# ADAPTER.net
KiCad netlist of a schematic drawn in EAGLE
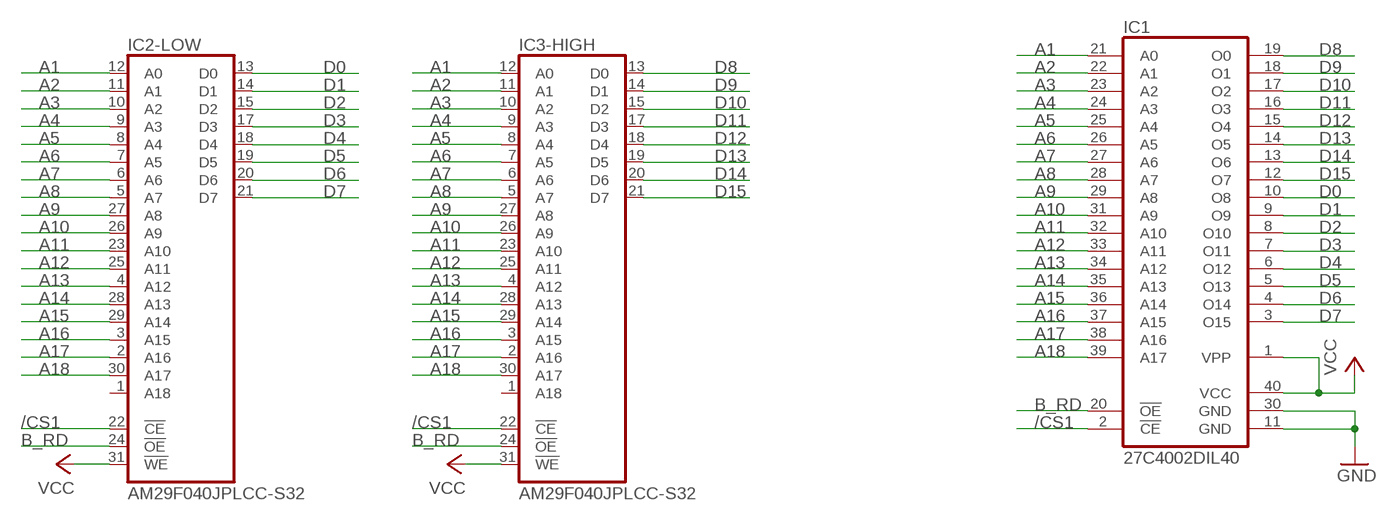
[diagram p0: schematic, sheet 1]

(export (version "E")
  (design (tool "Eeschema 10.0.6"))
  (components
    (comp (ref "IC1")
      (value "27C4002DIL40")
      (footprint "eagle-import:DIL40")
      (libsource (lib "eagle-import") (part "27C4002DIL40"))
    )
    (comp (ref "IC2-LOW")
      (value "AM29F040JPLCC-S32")
      (footprint "eagle-import:PLCC-S32")
      (libsource (lib "eagle-import") (part "AM29F040JPLCC-S32"))
    )
    (comp (ref "IC3-HIGH")
      (value "AM29F040JPLCC-S32")
      (footprint "eagle-import:PLCC-S32")
      (libsource (lib "eagle-import") (part "AM29F040JPLCC-S32"))
    )
  )
  (nets
    (net (code "1") (name "/A1") (class "Default")
      (node (ref "IC1") (pin "21") (pinfunction "A0_21") (pintype "input"))
      (node (ref "IC2-LOW") (pin "12") (pinfunction "A0_12") (pintype "input"))
      (node (ref "IC3-HIGH") (pin "12") (pinfunction "A0_12") (pintype "input"))
    )
    (net (code "2") (name "/A2") (class "Default")
      (node (ref "IC1") (pin "22") (pinfunction "A1_22") (pintype "input"))
      (node (ref "IC2-LOW") (pin "11") (pinfunction "A1_11") (pintype "input"))
      (node (ref "IC3-HIGH") (pin "11") (pinfunction "A1_11") (pintype "input"))
    )
    (net (code "3") (name "/A3") (class "Default")
      (node (ref "IC1") (pin "23") (pinfunction "A2_23") (pintype "input"))
      (node (ref "IC2-LOW") (pin "10") (pinfunction "A2_10") (pintype "input"))
      (node (ref "IC3-HIGH") (pin "10") (pinfunction "A2_10") (pintype "input"))
    )
    (net (code "4") (name "/A4") (class "Default")
      (node (ref "IC1") (pin "24") (pinfunction "A3_24") (pintype "input"))
      (node (ref "IC2-LOW") (pin "9") (pinfunction "A3_9") (pintype "input"))
      (node (ref "IC3-HIGH") (pin "9") (pinfunction "A3_9") (pintype "input"))
    )
    (net (code "5") (name "/A5") (class "Default")
      (node (ref "IC1") (pin "25") (pinfunction "A4_25") (pintype "input"))
      (node (ref "IC2-LOW") (pin "8") (pinfunction "A4_8") (pintype "input"))
      (node (ref "IC3-HIGH") (pin "8") (pinfunction "A4_8") (pintype "input"))
    )
    (net (code "6") (name "/A6") (class "Default")
      (node (ref "IC1") (pin "26") (pinfunction "A5_26") (pintype "input"))
      (node (ref "IC2-LOW") (pin "7") (pinfunction "A5_7") (pintype "input"))
      (node (ref "IC3-HIGH") (pin "7") (pinfunction "A5_7") (pintype "input"))
    )
    (net (code "7") (name "/A7") (class "Default")
      (node (ref "IC1") (pin "27") (pinfunction "A6_27") (pintype "input"))
      (node (ref "IC2-LOW") (pin "6") (pinfunction "A6_6") (pintype "input"))
      (node (ref "IC3-HIGH") (pin "6") (pinfunction "A6_6") (pintype "input"))
    )
    (net (code "8") (name "/A8") (class "Default")
      (node (ref "IC1") (pin "28") (pinfunction "A7_28") (pintype "input"))
      (node (ref "IC2-LOW") (pin "5") (pinfunction "A7_5") (pintype "input"))
      (node (ref "IC3-HIGH") (pin "5") (pinfunction "A7_5") (pintype "input"))
    )
    (net (code "9") (name "/A9") (class "Default")
      (node (ref "IC1") (pin "29") (pinfunction "A8_29") (pintype "input"))
      (node (ref "IC2-LOW") (pin "27") (pinfunction "A8_27") (pintype "input"))
      (node (ref "IC3-HIGH") (pin "27") (pinfunction "A8_27") (pintype "input"))
    )
    (net (code "10") (name "/A10") (class "Default")
      (node (ref "IC1") (pin "31") (pinfunction "A9_31") (pintype "input"))
      (node (ref "IC2-LOW") (pin "26") (pinfunction "A9_26") (pintype "input"))
      (node (ref "IC3-HIGH") (pin "26") (pinfunction "A9_26") (pintype "input"))
    )
    (net (code "11") (name "/A11") (class "Default")
      (node (ref "IC1") (pin "32") (pinfunction "A10_32") (pintype "input"))
      (node (ref "IC2-LOW") (pin "23") (pinfunction "A10_23") (pintype "input"))
      (node (ref "IC3-HIGH") (pin "23") (pinfunction "A10_23") (pintype "input"))
    )
    (net (code "12") (name "/A12") (class "Default")
      (node (ref "IC1") (pin "33") (pinfunction "A11_33") (pintype "input"))
      (node (ref "IC2-LOW") (pin "25") (pinfunction "A11_25") (pintype "input"))
      (node (ref "IC3-HIGH") (pin "25") (pinfunction "A11_25") (pintype "input"))
    )
    (net (code "13") (name "/A13") (class "Default")
      (node (ref "IC1") (pin "34") (pinfunction "A12_34") (pintype "input"))
      (node (ref "IC2-LOW") (pin "4") (pinfunction "A12_4") (pintype "input"))
      (node (ref "IC3-HIGH") (pin "4") (pinfunction "A12_4") (pintype "input"))
    )
    (net (code "14") (name "/A14") (class "Default")
      (node (ref "IC1") (pin "35") (pinfunction "A13_35") (pintype "input"))
      (node (ref "IC2-LOW") (pin "28") (pinfunction "A13_28") (pintype "input"))
      (node (ref "IC3-HIGH") (pin "28") (pinfunction "A13_28") (pintype "input"))
    )
    (net (code "15") (name "/A15") (class "Default")
      (node (ref "IC1") (pin "36") (pinfunction "A14_36") (pintype "input"))
      (node (ref "IC2-LOW") (pin "29") (pinfunction "A14_29") (pintype "input"))
      (node (ref "IC3-HIGH") (pin "29") (pinfunction "A14_29") (pintype "input"))
    )
    (net (code "16") (name "/A16") (class "Default")
      (node (ref "IC1") (pin "37") (pinfunction "A15_37") (pintype "input"))
      (node (ref "IC2-LOW") (pin "3") (pinfunction "A15_3") (pintype "input"))
      (node (ref "IC3-HIGH") (pin "3") (pinfunction "A15_3") (pintype "input"))
    )
    (net (code "17") (name "/A17") (class "Default")
      (node (ref "IC1") (pin "38") (pinfunction "A16_38") (pintype "input"))
      (node (ref "IC2-LOW") (pin "2") (pinfunction "A16_2") (pintype "input"))
      (node (ref "IC3-HIGH") (pin "2") (pinfunction "A16_2") (pintype "input"))
    )
    (net (code "18") (name "/A18") (class "Default")
      (node (ref "IC1") (pin "39") (pinfunction "A17_39") (pintype "input"))
      (node (ref "IC2-LOW") (pin "30") (pinfunction "A17_30") (pintype "input"))
      (node (ref "IC3-HIGH") (pin "30") (pinfunction "A17_30") (pintype "input"))
    )
    (net (code "19") (name "/B_RD") (class "Default")
      (node (ref "IC1") (pin "20") (pinfunction "~{OE}_20") (pintype "input"))
      (node (ref "IC2-LOW") (pin "24") (pinfunction "~{OE}_24") (pintype "input"))
      (node (ref "IC3-HIGH") (pin "24") (pinfunction "~{OE}_24") (pintype "input"))
    )
    (net (code "20") (name "/D0") (class "Default")
      (node (ref "IC1") (pin "10") (pinfunction "O8_10") (pintype "tri_state"))
      (node (ref "IC2-LOW") (pin "13") (pinfunction "D0_13") (pintype "tri_state"))
    )
    (net (code "21") (name "/D1") (class "Default")
      (node (ref "IC1") (pin "9") (pinfunction "O9_9") (pintype "tri_state"))
      (node (ref "IC2-LOW") (pin "14") (pinfunction "D1_14") (pintype "tri_state"))
    )
    (net (code "22") (name "/D2") (class "Default")
      (node (ref "IC1") (pin "8") (pinfunction "O10_8") (pintype "tri_state"))
      (node (ref "IC2-LOW") (pin "15") (pinfunction "D2_15") (pintype "tri_state"))
    )
    (net (code "23") (name "/D3") (class "Default")
      (node (ref "IC1") (pin "7") (pinfunction "O11_7") (pintype "tri_state"))
      (node (ref "IC2-LOW") (pin "17") (pinfunction "D3_17") (pintype "tri_state"))
    )
    (net (code "24") (name "/D4") (class "Default")
      (node (ref "IC1") (pin "6") (pinfunction "O12_6") (pintype "tri_state"))
      (node (ref "IC2-LOW") (pin "18") (pinfunction "D4_18") (pintype "tri_state"))
    )
    (net (code "25") (name "/D5") (class "Default")
      (node (ref "IC1") (pin "5") (pinfunction "O13_5") (pintype "tri_state"))
      (node (ref "IC2-LOW") (pin "19") (pinfunction "D5_19") (pintype "tri_state"))
    )
    (net (code "26") (name "/D6") (class "Default")
      (node (ref "IC1") (pin "4") (pinfunction "O14_4") (pintype "tri_state"))
      (node (ref "IC2-LOW") (pin "20") (pinfunction "D6_20") (pintype "tri_state"))
    )
    (net (code "27") (name "/D7") (class "Default")
      (node (ref "IC1") (pin "3") (pinfunction "O15_3") (pintype "tri_state"))
      (node (ref "IC2-LOW") (pin "21") (pinfunction "D7_21") (pintype "tri_state"))
    )
    (net (code "28") (name "/D8") (class "Default")
      (node (ref "IC1") (pin "19") (pinfunction "O0_19") (pintype "tri_state"))
      (node (ref "IC3-HIGH") (pin "13") (pinfunction "D0_13") (pintype "tri_state"))
    )
    (net (code "29") (name "/D9") (class "Default")
      (node (ref "IC1") (pin "18") (pinfunction "O1_18") (pintype "tri_state"))
      (node (ref "IC3-HIGH") (pin "14") (pinfunction "D1_14") (pintype "tri_state"))
    )
    (net (code "30") (name "/D10") (class "Default")
      (node (ref "IC1") (pin "17") (pinfunction "O2_17") (pintype "tri_state"))
      (node (ref "IC3-HIGH") (pin "15") (pinfunction "D2_15") (pintype "tri_state"))
    )
    (net (code "31") (name "/D11") (class "Default")
      (node (ref "IC1") (pin "16") (pinfunction "O3_16") (pintype "tri_state"))
      (node (ref "IC3-HIGH") (pin "17") (pinfunction "D3_17") (pintype "tri_state"))
    )
    (net (code "32") (name "/D12") (class "Default")
      (node (ref "IC1") (pin "15") (pinfunction "O4_15") (pintype "tri_state"))
      (node (ref "IC3-HIGH") (pin "18") (pinfunction "D4_18") (pintype "tri_state"))
    )
    (net (code "33") (name "/D13") (class "Default")
      (node (ref "IC1") (pin "14") (pinfunction "O5_14") (pintype "tri_state"))
      (node (ref "IC3-HIGH") (pin "19") (pinfunction "D5_19") (pintype "tri_state"))
    )
    (net (code "34") (name "/D14") (class "Default")
      (node (ref "IC1") (pin "13") (pinfunction "O6_13") (pintype "tri_state"))
      (node (ref "IC3-HIGH") (pin "20") (pinfunction "D6_20") (pintype "tri_state"))
    )
    (net (code "35") (name "/D15") (class "Default")
      (node (ref "IC1") (pin "12") (pinfunction "O7_12") (pintype "tri_state"))
      (node (ref "IC3-HIGH") (pin "21") (pinfunction "D7_21") (pintype "tri_state"))
    )
    (net (code "36") (name "/{slash}CS1") (class "Default")
      (node (ref "IC1") (pin "2") (pinfunction "~{CE}_2") (pintype "input"))
      (node (ref "IC2-LOW") (pin "22") (pinfunction "~{CE}_22") (pintype "input"))
      (node (ref "IC3-HIGH") (pin "22") (pinfunction "~{CE}_22") (pintype "input"))
    )
    (net (code "37") (name "GND") (class "Default")
      (node (ref "IC1") (pin "11") (pinfunction "GND_11") (pintype "power_in"))
      (node (ref "IC1") (pin "30") (pinfunction "GND_30") (pintype "power_in"))
    )
    (net (code "38") (name "VCC") (class "Default")
      (node (ref "IC1") (pin "1") (pinfunction "VPP_1") (pintype "passive"))
      (node (ref "IC1") (pin "40") (pinfunction "VCC_40") (pintype "power_in"))
      (node (ref "IC2-LOW") (pin "31") (pinfunction "~{WE}_31") (pintype "input"))
      (node (ref "IC3-HIGH") (pin "31") (pinfunction "~{WE}_31") (pintype "input"))
    )
    (net (code "39") (name "unconnected-(IC2-LOWA-A18-Pad1)") (class "Default")
      (node (ref "IC2-LOW") (pin "1") (pinfunction "A18_1") (pintype "input"))
    )
    (net (code "40") (name "unconnected-(IC3-HIGHA-A18-Pad1)") (class "Default")
      (node (ref "IC3-HIGH") (pin "1") (pinfunction "A18_1") (pintype "input"))
    )
  )
)
